# IV_PogopinConnector.net
KiCad netlist of a schematic drawn in Altium Designer
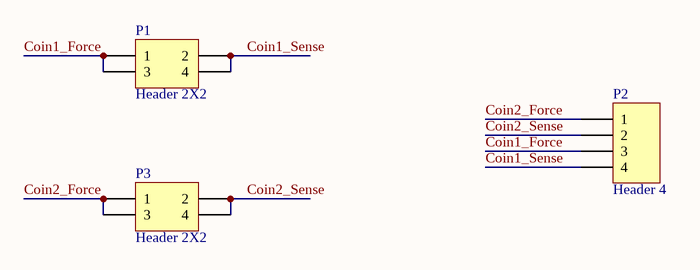
[diagram p0: IV_PogopinConnector.SchDoc]

(export (version "E")
  (design (tool "Eeschema 10.0.6"))
  (components
    (comp (ref "P1")
      (value "Header 2X2")
      (footprint "HDR2X2")
      (description "Header, 2-Pin, Dual row")
      (fields (field (name "PUBLISHER") "Altium Limited"))
      (libsource (lib "Miscellaneous Connectors") (part "Header 2X2"))
    )
    (comp (ref "P2")
      (value "Header 4")
      (footprint "HDR1X4")
      (description "Header, 4-Pin")
      (fields (field (name "PUBLISHER") "Altium Limited"))
      (libsource (lib "Miscellaneous Connectors") (part "Header 4"))
    )
    (comp (ref "P3")
      (value "Header 2X2")
      (footprint "HDR2X2")
      (description "Header, 2-Pin, Dual row")
      (fields (field (name "PUBLISHER") "Altium Limited"))
      (libsource (lib "Miscellaneous Connectors") (part "Header 2X2"))
    )
  )
  (nets
    (net (code "1") (name "/Coin1_Force") (class "Default")
      (node (ref "P1") (pin "1") (pinfunction "1_1") (pintype "passive"))
      (node (ref "P1") (pin "3") (pinfunction "3_3") (pintype "passive"))
      (node (ref "P2") (pin "3") (pinfunction "3_3") (pintype "passive"))
    )
    (net (code "2") (name "/Coin1_Sense") (class "Default")
      (node (ref "P1") (pin "2") (pinfunction "2_2") (pintype "passive"))
      (node (ref "P1") (pin "4") (pinfunction "4_4") (pintype "passive"))
      (node (ref "P2") (pin "4") (pinfunction "4_4") (pintype "passive"))
    )
    (net (code "3") (name "/Coin2_Force") (class "Default")
      (node (ref "P2") (pin "1") (pinfunction "1_1") (pintype "passive"))
      (node (ref "P3") (pin "1") (pinfunction "1_1") (pintype "passive"))
      (node (ref "P3") (pin "3") (pinfunction "3_3") (pintype "passive"))
    )
    (net (code "4") (name "/Coin2_Sense") (class "Default")
      (node (ref "P2") (pin "2") (pinfunction "2_2") (pintype "passive"))
      (node (ref "P3") (pin "2") (pinfunction "2_2") (pintype "passive"))
      (node (ref "P3") (pin "4") (pinfunction "4_4") (pintype "passive"))
    )
  )
)
